# imu.net
KiCad netlist of a schematic drawn in EAGLE
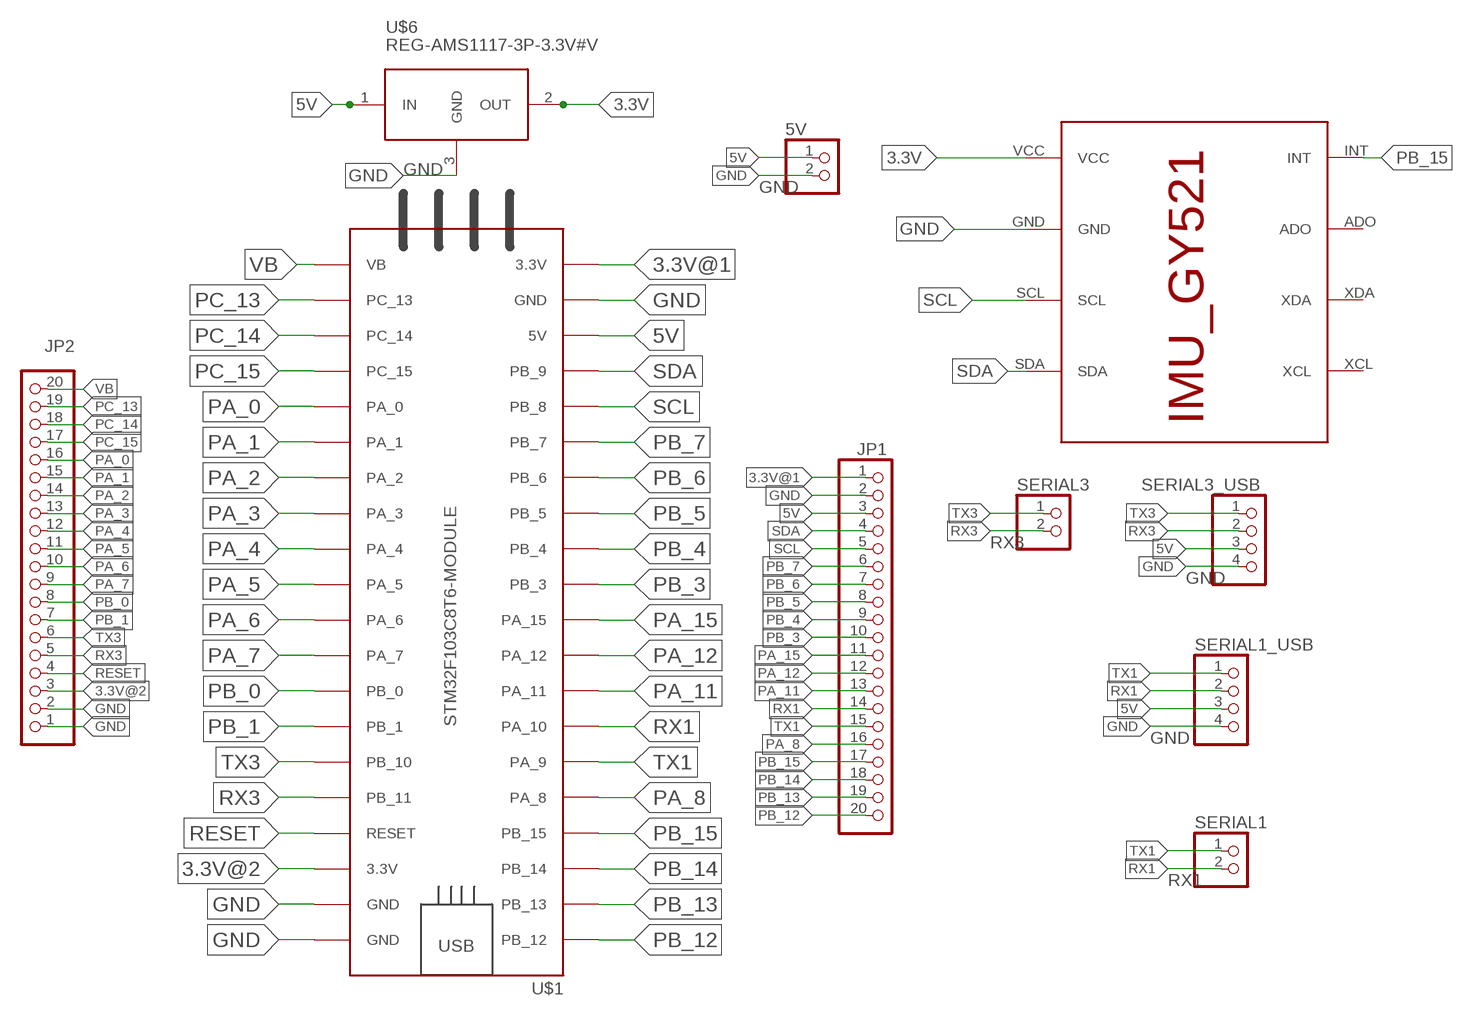
[diagram p0: schematic, sheet 1]

(export (version "E")
  (design (tool "Eeschema 10.0.6"))
  (components
    (comp (ref "5V")
      (value "PINHD-2_DATA")
      (footprint "eagle-import:1X02_DATA")
      (libsource (lib "eagle-import") (part "PINHD-2_DATA"))
    )
    (comp (ref "JP1")
      (value "PINHD-1X20")
      (footprint "eagle-import:1X20")
      (libsource (lib "eagle-import") (part "PINHD-1X20"))
    )
    (comp (ref "JP2")
      (value "PINHD-1X20")
      (footprint "eagle-import:1X20")
      (libsource (lib "eagle-import") (part "PINHD-1X20"))
    )
    (comp (ref "SERIAL1")
      (value "PINHD-2_DATA")
      (footprint "eagle-import:1X02_DATA")
      (libsource (lib "eagle-import") (part "PINHD-2_DATA"))
    )
    (comp (ref "SERIAL1_USB")
      (value "PINHD-4_DATA")
      (footprint "eagle-import:1X04_DATA")
      (libsource (lib "eagle-import") (part "PINHD-4_DATA"))
    )
    (comp (ref "SERIAL3")
      (value "PINHD-2_DATA")
      (footprint "eagle-import:1X02_DATA")
      (libsource (lib "eagle-import") (part "PINHD-2_DATA"))
    )
    (comp (ref "SERIAL3_USB")
      (value "PINHD-4_DATA")
      (footprint "eagle-import:1X04_DATA")
      (libsource (lib "eagle-import") (part "PINHD-4_DATA"))
    )
    (comp (ref "U$1")
      (value "STM32F103C8T6-MODULE")
      (footprint "eagle-import:STM32F103C8T6-MODULE")
      (libsource (lib "eagle-import") (part "STM32F103C8T6-MODULE"))
    )
    (comp (ref "U$2")
      (value "IMU_ROBOCON_GY521")
      (footprint "eagle-import:IMU_GY521")
      (libsource (lib "eagle-import") (part "IMU_ROBOCON_GY521"))
    )
    (comp (ref "U$6")
      (value "REG-AMS1117-3P-3.3V#V")
      (footprint "eagle-import:REG-AMS1117-3P#V")
      (libsource (lib "eagle-import") (part "REG-AMS1117-3P-#V3.3V"))
    )
  )
  (nets
    (net (code "1") (name "3.3V") (class "Default")
      (node (ref "U$2") (pin "VCC") (pinfunction "VCC_VCC") (pintype "bidirectional"))
      (node (ref "U$6") (pin "2") (pinfunction "OUT_2") (pintype "bidirectional"))
    )
    (net (code "2") (name "3.3V@1") (class "Default")
      (node (ref "JP1") (pin "1") (pinfunction "1_1") (pintype "passive"))
      (node (ref "U$1") (pin "3.3V_1") (pinfunction "3.3V_3.3V_1") (pintype "bidirectional"))
    )
    (net (code "3") (name "3.3V@2") (class "Default")
      (node (ref "JP2") (pin "3") (pinfunction "3_3") (pintype "passive"))
      (node (ref "U$1") (pin "3.3V_2") (pinfunction "3.3V_3.3V_2") (pintype "bidirectional"))
    )
    (net (code "4") (name "5V") (class "Default")
      (node (ref "5V") (pin "1") (pinfunction "1_1") (pintype "passive"))
      (node (ref "JP1") (pin "3") (pinfunction "3_3") (pintype "passive"))
      (node (ref "SERIAL1_USB") (pin "3") (pinfunction "3_3") (pintype "passive"))
      (node (ref "SERIAL3_USB") (pin "3") (pinfunction "3_3") (pintype "passive"))
      (node (ref "U$1") (pin "5V") (pinfunction "5V_5V") (pintype "bidirectional"))
      (node (ref "U$6") (pin "1") (pinfunction "IN_1") (pintype "bidirectional"))
    )
    (net (code "5") (name "GND") (class "Default")
      (node (ref "5V") (pin "2") (pinfunction "2_2") (pintype "passive"))
      (node (ref "JP1") (pin "2") (pinfunction "2_2") (pintype "passive"))
      (node (ref "JP2") (pin "1") (pinfunction "1_1") (pintype "passive"))
      (node (ref "JP2") (pin "2") (pinfunction "2_2") (pintype "passive"))
      (node (ref "SERIAL1_USB") (pin "4") (pinfunction "4_4") (pintype "passive"))
      (node (ref "SERIAL3_USB") (pin "4") (pinfunction "4_4") (pintype "passive"))
      (node (ref "U$1") (pin "GND_1") (pinfunction "GND_GND_1") (pintype "bidirectional"))
      (node (ref "U$1") (pin "GND_2") (pinfunction "GND_GND_2") (pintype "bidirectional"))
      (node (ref "U$1") (pin "GND_3") (pinfunction "GND_GND_3") (pintype "power_in"))
      (node (ref "U$2") (pin "GND") (pinfunction "GND_GND") (pintype "bidirectional"))
      (node (ref "U$6") (pin "3") (pinfunction "GND_3") (pintype "bidirectional"))
    )
    (net (code "6") (name "PA_0") (class "Default")
      (node (ref "JP2") (pin "16") (pinfunction "16_16") (pintype "passive"))
      (node (ref "U$1") (pin "PA_0") (pinfunction "PA_0_PA_0") (pintype "bidirectional"))
    )
    (net (code "7") (name "PA_1") (class "Default")
      (node (ref "JP2") (pin "15") (pinfunction "15_15") (pintype "passive"))
      (node (ref "U$1") (pin "PA_1") (pinfunction "PA_1_PA_1") (pintype "bidirectional"))
    )
    (net (code "8") (name "PA_2") (class "Default")
      (node (ref "JP2") (pin "14") (pinfunction "14_14") (pintype "passive"))
      (node (ref "U$1") (pin "PA_2") (pinfunction "PA_2_PA_2") (pintype "bidirectional"))
    )
    (net (code "9") (name "PA_3") (class "Default")
      (node (ref "JP2") (pin "13") (pinfunction "13_13") (pintype "passive"))
      (node (ref "U$1") (pin "PA_3") (pinfunction "PA_3_PA_3") (pintype "bidirectional"))
    )
    (net (code "10") (name "PA_4") (class "Default")
      (node (ref "JP2") (pin "12") (pinfunction "12_12") (pintype "passive"))
      (node (ref "U$1") (pin "PA_4") (pinfunction "PA_4_PA_4") (pintype "bidirectional"))
    )
    (net (code "11") (name "PA_5") (class "Default")
      (node (ref "JP2") (pin "11") (pinfunction "11_11") (pintype "passive"))
      (node (ref "U$1") (pin "PA_5") (pinfunction "PA_5_PA_5") (pintype "bidirectional"))
    )
    (net (code "12") (name "PA_6") (class "Default")
      (node (ref "JP2") (pin "10") (pinfunction "10_10") (pintype "passive"))
      (node (ref "U$1") (pin "PA_6") (pinfunction "PA_6_PA_6") (pintype "bidirectional"))
    )
    (net (code "13") (name "PA_7") (class "Default")
      (node (ref "JP2") (pin "9") (pinfunction "9_9") (pintype "passive"))
      (node (ref "U$1") (pin "PA_7") (pinfunction "PA_7_PA_7") (pintype "bidirectional"))
    )
    (net (code "14") (name "PA_8") (class "Default")
      (node (ref "JP1") (pin "16") (pinfunction "16_16") (pintype "passive"))
      (node (ref "U$1") (pin "PA_8") (pinfunction "PA_8_PA_8") (pintype "bidirectional"))
    )
    (net (code "15") (name "PA_11") (class "Default")
      (node (ref "JP1") (pin "13") (pinfunction "13_13") (pintype "passive"))
      (node (ref "U$1") (pin "PA_11") (pinfunction "PA_11_PA_11") (pintype "bidirectional"))
    )
    (net (code "16") (name "PA_12") (class "Default")
      (node (ref "JP1") (pin "12") (pinfunction "12_12") (pintype "passive"))
      (node (ref "U$1") (pin "PA_12") (pinfunction "PA_12_PA_12") (pintype "bidirectional"))
    )
    (net (code "17") (name "PA_15") (class "Default")
      (node (ref "JP1") (pin "11") (pinfunction "11_11") (pintype "passive"))
      (node (ref "U$1") (pin "PA_15") (pinfunction "PA_15_PA_15") (pintype "bidirectional"))
    )
    (net (code "18") (name "PB_0") (class "Default")
      (node (ref "JP2") (pin "8") (pinfunction "8_8") (pintype "passive"))
      (node (ref "U$1") (pin "PB_0") (pinfunction "PB_0_PB_0") (pintype "bidirectional"))
    )
    (net (code "19") (name "PB_1") (class "Default")
      (node (ref "JP2") (pin "7") (pinfunction "7_7") (pintype "passive"))
      (node (ref "U$1") (pin "PB_1") (pinfunction "PB_1_PB_1") (pintype "bidirectional"))
    )
    (net (code "20") (name "PB_3") (class "Default")
      (node (ref "JP1") (pin "10") (pinfunction "10_10") (pintype "passive"))
      (node (ref "U$1") (pin "PB_3") (pinfunction "PB_3_PB_3") (pintype "bidirectional"))
    )
    (net (code "21") (name "PB_4") (class "Default")
      (node (ref "JP1") (pin "9") (pinfunction "9_9") (pintype "passive"))
      (node (ref "U$1") (pin "PB_4") (pinfunction "PB_4_PB_4") (pintype "bidirectional"))
    )
    (net (code "22") (name "PB_5") (class "Default")
      (node (ref "JP1") (pin "8") (pinfunction "8_8") (pintype "passive"))
      (node (ref "U$1") (pin "PB_5") (pinfunction "PB_5_PB_5") (pintype "bidirectional"))
    )
    (net (code "23") (name "PB_6") (class "Default")
      (node (ref "JP1") (pin "7") (pinfunction "7_7") (pintype "passive"))
      (node (ref "U$1") (pin "PB_6") (pinfunction "PB_6_PB_6") (pintype "bidirectional"))
    )
    (net (code "24") (name "PB_7") (class "Default")
      (node (ref "JP1") (pin "6") (pinfunction "6_6") (pintype "passive"))
      (node (ref "U$1") (pin "PB_7") (pinfunction "PB_7_PB_7") (pintype "bidirectional"))
    )
    (net (code "25") (name "PB_12") (class "Default")
      (node (ref "JP1") (pin "20") (pinfunction "20_20") (pintype "passive"))
      (node (ref "U$1") (pin "PB_12") (pinfunction "PB_12_PB_12") (pintype "bidirectional"))
    )
    (net (code "26") (name "PB_13") (class "Default")
      (node (ref "JP1") (pin "19") (pinfunction "19_19") (pintype "passive"))
      (node (ref "U$1") (pin "PB_13") (pinfunction "PB_13_PB_13") (pintype "bidirectional"))
    )
    (net (code "27") (name "PB_14") (class "Default")
      (node (ref "JP1") (pin "18") (pinfunction "18_18") (pintype "passive"))
      (node (ref "U$1") (pin "PB_14") (pinfunction "PB_14_PB_14") (pintype "bidirectional"))
    )
    (net (code "28") (name "PB_15") (class "Default")
      (node (ref "JP1") (pin "17") (pinfunction "17_17") (pintype "passive"))
      (node (ref "U$1") (pin "PB_15") (pinfunction "PB_15_PB_15") (pintype "bidirectional"))
      (node (ref "U$2") (pin "INT") (pinfunction "INT_INT") (pintype "bidirectional"))
    )
    (net (code "29") (name "PC_13") (class "Default")
      (node (ref "JP2") (pin "19") (pinfunction "19_19") (pintype "passive"))
      (node (ref "U$1") (pin "PC_13") (pinfunction "PC_13_PC_13") (pintype "bidirectional"))
    )
    (net (code "30") (name "PC_14") (class "Default")
      (node (ref "JP2") (pin "18") (pinfunction "18_18") (pintype "passive"))
      (node (ref "U$1") (pin "PC_14") (pinfunction "PC_14_PC_14") (pintype "bidirectional"))
    )
    (net (code "31") (name "PC_15") (class "Default")
      (node (ref "JP2") (pin "17") (pinfunction "17_17") (pintype "passive"))
      (node (ref "U$1") (pin "PC_15") (pinfunction "PC_15_PC_15") (pintype "bidirectional"))
    )
    (net (code "32") (name "RESET") (class "Default")
      (node (ref "JP2") (pin "4") (pinfunction "4_4") (pintype "passive"))
      (node (ref "U$1") (pin "RESET") (pinfunction "RESET_RESET") (pintype "bidirectional"))
    )
    (net (code "33") (name "RX1") (class "Default")
      (node (ref "JP1") (pin "14") (pinfunction "14_14") (pintype "passive"))
      (node (ref "SERIAL1") (pin "2") (pinfunction "2_2") (pintype "passive"))
      (node (ref "SERIAL1_USB") (pin "2") (pinfunction "2_2") (pintype "passive"))
      (node (ref "U$1") (pin "PA_10") (pinfunction "PA_10_PA_10") (pintype "bidirectional"))
    )
    (net (code "34") (name "RX3") (class "Default")
      (node (ref "JP2") (pin "5") (pinfunction "5_5") (pintype "passive"))
      (node (ref "SERIAL3") (pin "2") (pinfunction "2_2") (pintype "passive"))
      (node (ref "SERIAL3_USB") (pin "2") (pinfunction "2_2") (pintype "passive"))
      (node (ref "U$1") (pin "PB_11") (pinfunction "PB_11_PB_11") (pintype "bidirectional"))
    )
    (net (code "35") (name "SCL") (class "Default")
      (node (ref "JP1") (pin "5") (pinfunction "5_5") (pintype "passive"))
      (node (ref "U$1") (pin "PB_8") (pinfunction "PB_8_PB_8") (pintype "bidirectional"))
      (node (ref "U$2") (pin "SCL") (pinfunction "SCL_SCL") (pintype "bidirectional"))
    )
    (net (code "36") (name "SDA") (class "Default")
      (node (ref "JP1") (pin "4") (pinfunction "4_4") (pintype "passive"))
      (node (ref "U$1") (pin "PB_9") (pinfunction "PB_9_PB_9") (pintype "bidirectional"))
      (node (ref "U$2") (pin "SDA") (pinfunction "SDA_SDA") (pintype "bidirectional"))
    )
    (net (code "37") (name "TX1") (class "Default")
      (node (ref "JP1") (pin "15") (pinfunction "15_15") (pintype "passive"))
      (node (ref "SERIAL1") (pin "1") (pinfunction "1_1") (pintype "passive"))
      (node (ref "SERIAL1_USB") (pin "1") (pinfunction "1_1") (pintype "passive"))
      (node (ref "U$1") (pin "PA_9") (pinfunction "PA_9_PA_9") (pintype "bidirectional"))
    )
    (net (code "38") (name "TX3") (class "Default")
      (node (ref "JP2") (pin "6") (pinfunction "6_6") (pintype "passive"))
      (node (ref "SERIAL3") (pin "1") (pinfunction "1_1") (pintype "passive"))
      (node (ref "SERIAL3_USB") (pin "1") (pinfunction "1_1") (pintype "passive"))
      (node (ref "U$1") (pin "PB_10") (pinfunction "PB_10_PB_10") (pintype "bidirectional"))
    )
    (net (code "39") (name "VB") (class "Default")
      (node (ref "JP2") (pin "20") (pinfunction "20_20") (pintype "passive"))
      (node (ref "U$1") (pin "VB") (pinfunction "VB_VB") (pintype "bidirectional"))
    )
    (net (code "40") (name "unconnected-(U$2-PadADO)") (class "Default")
      (node (ref "U$2") (pin "ADO") (pinfunction "ADO_ADO") (pintype "bidirectional"))
    )
    (net (code "41") (name "unconnected-(U$2-PadXCL)") (class "Default")
      (node (ref "U$2") (pin "XCL") (pinfunction "XCL_XCL") (pintype "bidirectional"))
    )
    (net (code "42") (name "unconnected-(U$2-PadXDA)") (class "Default")
      (node (ref "U$2") (pin "XDA") (pinfunction "XDA_XDA") (pintype "bidirectional"))
    )
  )
)
